# FT232.net
KiCad netlist of a schematic drawn in Altium Designer
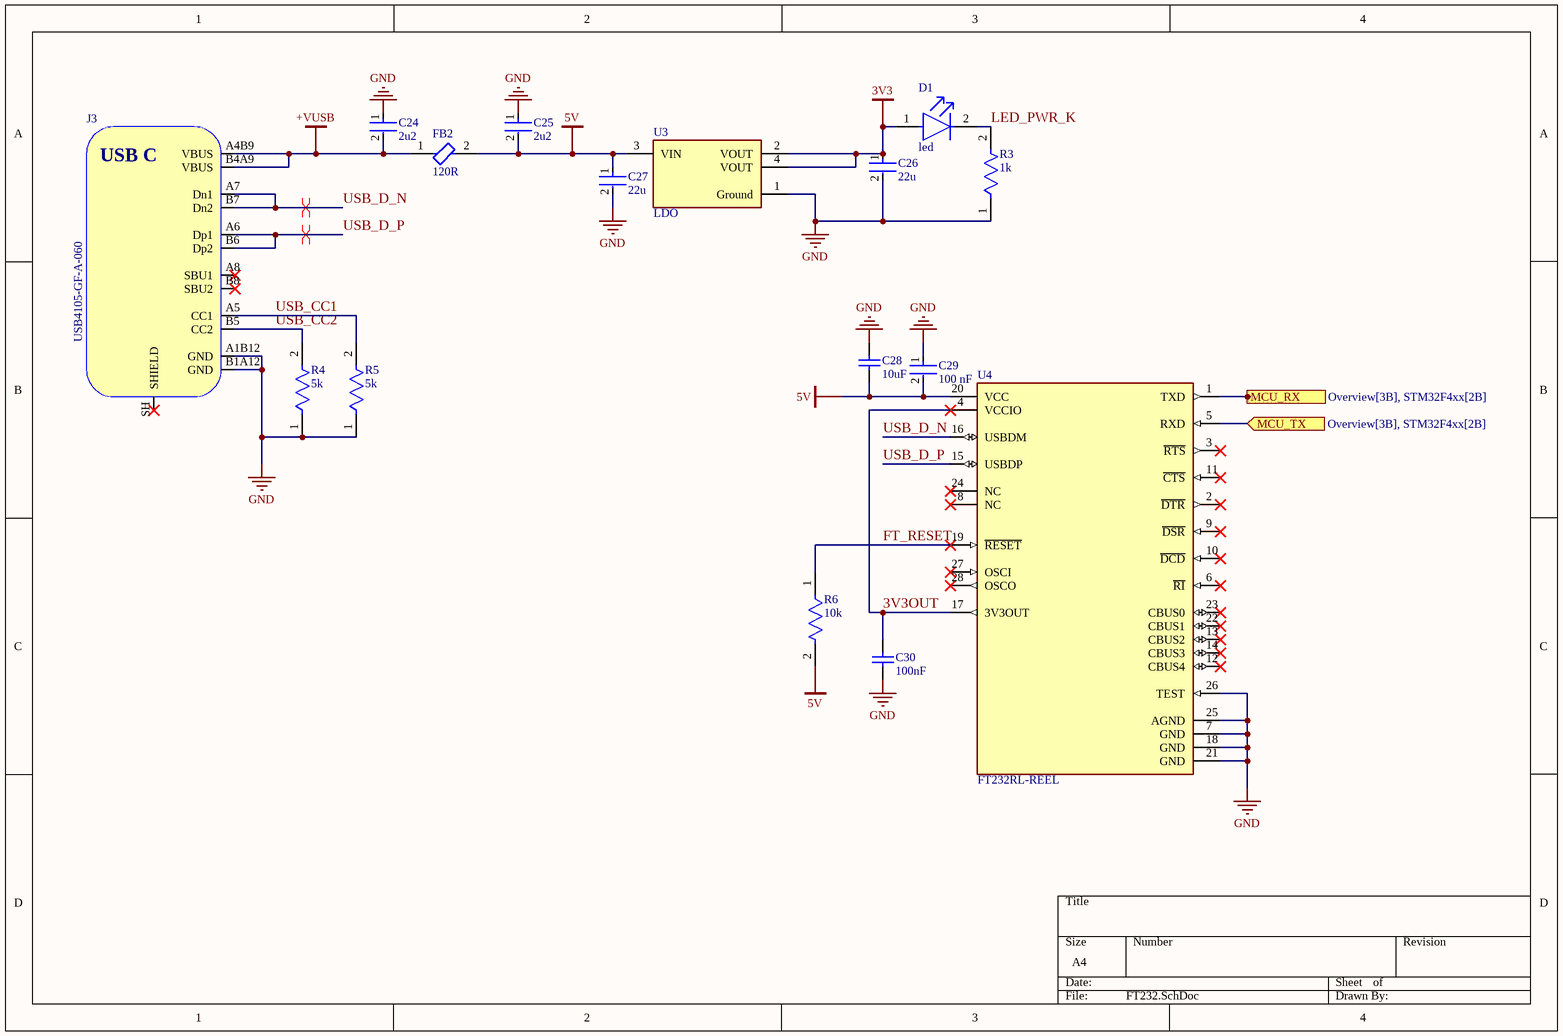
[diagram p0: FT232.SchDoc]

(export (version "E")
  (design (tool "Eeschema 10.0.6"))
  (components
    (comp (ref "C24")
      (value "2u2")
      (footprint "FP-CC0603-DA-MFG")
      (description "CAP CER 2.2UF 16V X5R 0603")
      (fields (field (name "TOLERANCE") "0.2") (field (name "MANUFACTURER PART NUMBER") "CC0603MRX5R7BB225"))
      (libsource (lib "Altium Content Vault") (part "11868f565c42a9108669ba33697ecf6"))
    )
    (comp (ref "C25")
      (value "2u2")
      (footprint "FP-CC0603-DA-MFG")
      (description "CAP CER 2.2UF 16V X5R 0603")
      (fields (field (name "TOLERANCE") "0.2") (field (name "MANUFACTURER PART NUMBER") "CC0603MRX5R7BB225"))
      (libsource (lib "Altium Content Vault") (part "11868f565c42a9108669ba33697ecf6"))
    )
    (comp (ref "C26")
      (value "22u")
      (footprint "FP-GRM21B-0_2-e0_2_0_7-IPC_C")
      (description "Chip Multilayer Ceramic Capacitors for General Purpose, 0805, 22uF, X5R, 15%, 20%, 16V")
      (fields (field (name "TOLERANCE") "20%"))
      (libsource (lib "Altium Content Vault") (part "b4654b650e69147ec39a6b967a45e02"))
    )
    (comp (ref "C27")
      (value "22u")
      (footprint "FP-GRM21B-0_2-e0_2_0_7-IPC_C")
      (description "Chip Multilayer Ceramic Capacitors for General Purpose, 0805, 22uF, X5R, 15%, 20%, 16V")
      (fields (field (name "TOLERANCE") "20%"))
      (libsource (lib "Altium Content Vault") (part "b4654b650e69147ec39a6b967a45e02"))
    )
    (comp (ref "C28")
      (value "10uF")
      (footprint "CAPC0603(1608)100_M")
      (description "CAP 10uF 6.3V ±10% 0603 (1608 Metric) Thickness 1mm SMD")
      (fields (field (name "TOLERANCE") "Â±10%"))
      (libsource (lib "Altium Content Vault") (part "CAP"))
    )
    (comp (ref "C29")
      (value "100 nF")
      (footprint "FP-C0402-BB-MFG")
      (description "CAP CER 0.1UF 25V X5R 0402")
      (fields
        (field (name "TOLERANCE") "0.2")
        (field (name "OCTOPART") "https://octopart.com/c0402c104m3pac7867-kemet-84304880")
      )
      (libsource (lib "Altium Content Vault") (part "b4654b650e69147ec39a6b967a45e02"))
    )
    (comp (ref "C30")
      (value "100nF")
      (footprint "CAPC2013X145X50ML20T25")
      (fields (field (name "MANUFACTURER") "Kemet") (field (name "PART NUMBER") "C0805C104K5RACTM"))
      (libsource (lib "Altium Content Vault") (part "CAP"))
    )
    (comp (ref "D1")
      (value "led")
      (footprint "FP-SM0402GC-MFG")
      (description "LED GREEN CLEAR 0402 SMD")
      (libsource (lib "Altium Content Vault") (part "ab1c01a81903e929fc6c44469aada92"))
    )
    (comp (ref "FB2")
      (value "120R")
      (footprint "FP-BLM21-0_2-t0_85-e0_5-IPC_C")
      (description "Chip Ferrite Bead, 0805, 60Ω @ 100MHz, 0.02Ω, 25%, 1.9A")
      (libsource (lib "Altium Content Vault") (part "5f30dd21d616792df468990f7003faa"))
    )
    (comp (ref "J3")
      (value "USB4105-GF-A-060")
      (footprint "USB4105-GF-A-060")
      (description "USB Connector Type C SMT 12 Pin")
      (fields (field (name "MANUFACTURER") "GCT"))
      (libsource (lib "Schematic-Lib-PhilsLab") (part "USB4105-GF-A-060"))
    )
    (comp (ref "R3")
      (value "1k")
      (footprint "FP-MCS0402-IPC_C")
      (description "RES SMD 1.2K OHM 1% 1/10W 0402")
      (fields (field (name "TOLERANCE") "0.1%"))
      (libsource (lib "Altium Content Vault") (part "1029c3af85768c4190bb7ad29bc67b5"))
    )
    (comp (ref "R4")
      (value "5k")
      (footprint "FP-TFCR0603-IPC_A")
      (description "RES Thin Film,  4kΩ, 0.1%, 0.1W, 25ppm/°C, 0603")
      (libsource (lib "Altium Content Vault") (part "1029c3af85768c4190bb7ad29bc67b5"))
    )
    (comp (ref "R5")
      (value "5k")
      (footprint "FP-TFCR0603-IPC_A")
      (description "RES Thin Film,  4kΩ, 0.1%, 0.1W, 25ppm/°C, 0603")
      (libsource (lib "Altium Content Vault") (part "1029c3af85768c4190bb7ad29bc67b5"))
    )
    (comp (ref "R6")
      (value "10k")
      (footprint "FP-AC0603-IPC_A")
      (description "RES 10kΩ 5.00% 0.2W 0603")
      (libsource (lib "Altium Content Vault") (part "1029c3af85768c4190bb7ad29bc67b5"))
    )
    (comp (ref "U3")
      (value "LDO")
      (footprint "FP-AMS1117-IPC_C")
      (description "LDO Voltage Regulators 1A, 3.3V")
      (fields
        (field (name "MANUFACTURER PART NUMBER") "AMS1117-3.3")
        (field (name "OCTOPART") "https://octopart.com/ams1117-3.3-advanced+monolithic+systems-25899300")
      )
      (libsource (lib "Altium Content Vault") (part "8bdbb5f8e77002000e30dd2845d0354"))
    )
    (comp (ref "U4")
      (value "FT232RL-REEL")
      (footprint "FP-SSOP-28-MFG")
      (description "IC USB FS SERIAL UART 28-SSOP")
      (fields (field (name "VOLTAGE") "5V"))
      (libsource (lib "Altium Content Vault") (part "fa727c664f4d88ca0f1b580aa0dd901"))
    )
  )
  (nets
    (net (code "1") (name "+VUSB") (class "Default")
      (node (ref "C24") (pin "2") (pinfunction "2_2") (pintype "passive"))
      (node (ref "FB2") (pin "1") (pinfunction "1_1") (pintype "passive"))
      (node (ref "J3") (pin "A4B9") (pinfunction "VBUS_A4B9") (pintype "passive"))
      (node (ref "J3") (pin "B4A9") (pinfunction "VBUS_B4A9") (pintype "passive"))
    )
    (net (code "2") (name "/3V3OUT") (class "Default")
      (node (ref "C30") (pin "2") (pinfunction "2_2") (pintype "passive"))
      (node (ref "U4") (pin "17") (pinfunction "3V3OUT_17") (pintype "output"))
      (node (ref "U4") (pin "4") (pinfunction "VCCIO_4") (pintype "power_in"))
    )
    (net (code "3") (name "/FT_RESET") (class "Default")
      (node (ref "R6") (pin "1") (pinfunction "1_1") (pintype "passive"))
      (node (ref "U4") (pin "19") (pinfunction "~{RESET}_19") (pintype "input"))
    )
    (net (code "4") (name "/LED_PWR_K") (class "Default")
      (node (ref "D1") (pin "2") (pinfunction "C_2") (pintype "passive"))
      (node (ref "R3") (pin "2") (pinfunction "2_2") (pintype "passive"))
    )
    (net (code "5") (name "/MCU_RX") (class "Default")
      (node (ref "U4") (pin "1") (pinfunction "TXD_1") (pintype "output"))
    )
    (net (code "6") (name "/MCU_TX") (class "Default")
      (node (ref "U4") (pin "5") (pinfunction "RXD_5") (pintype "input"))
    )
    (net (code "7") (name "/USB_CC1") (class "Default")
      (node (ref "J3") (pin "A5") (pinfunction "CC1_A5") (pintype "passive"))
      (node (ref "R5") (pin "2") (pinfunction "2_2") (pintype "passive"))
    )
    (net (code "8") (name "/USB_CC2") (class "Default")
      (node (ref "J3") (pin "B5") (pinfunction "CC2_B5") (pintype "passive"))
      (node (ref "R4") (pin "2") (pinfunction "2_2") (pintype "passive"))
    )
    (net (code "9") (name "/USB_D_N") (class "Default")
      (node (ref "J3") (pin "A7") (pinfunction "Dn1_A7") (pintype "passive"))
      (node (ref "J3") (pin "B7") (pinfunction "Dn2_B7") (pintype "passive"))
      (node (ref "U4") (pin "16") (pinfunction "USBDM_16") (pintype "bidirectional"))
    )
    (net (code "10") (name "/USB_D_P") (class "Default")
      (node (ref "J3") (pin "A6") (pinfunction "Dp1_A6") (pintype "passive"))
      (node (ref "J3") (pin "B6") (pinfunction "Dp2_B6") (pintype "passive"))
      (node (ref "U4") (pin "15") (pinfunction "USBDP_15") (pintype "bidirectional"))
    )
    (net (code "11") (name "3V3") (class "Default")
      (node (ref "C26") (pin "1") (pinfunction "1_1") (pintype "passive"))
      (node (ref "D1") (pin "1") (pinfunction "A_1") (pintype "passive"))
      (node (ref "U3") (pin "2") (pinfunction "VOUT_2") (pintype "passive"))
      (node (ref "U3") (pin "4") (pinfunction "VOUT_4") (pintype "passive"))
    )
    (net (code "12") (name "5V") (class "Default")
      (node (ref "C25") (pin "2") (pinfunction "2_2") (pintype "passive"))
      (node (ref "C27") (pin "1") (pinfunction "1_1") (pintype "passive"))
      (node (ref "C28") (pin "1") (pinfunction "1_1") (pintype "passive"))
      (node (ref "C29") (pin "2") (pinfunction "2_2") (pintype "passive"))
      (node (ref "FB2") (pin "2") (pinfunction "2_2") (pintype "passive"))
      (node (ref "R6") (pin "2") (pinfunction "2_2") (pintype "passive"))
      (node (ref "U3") (pin "3") (pinfunction "VIN_3") (pintype "power_in"))
      (node (ref "U4") (pin "20") (pinfunction "VCC_20") (pintype "power_in"))
    )
    (net (code "13") (name "GND") (class "Default")
      (node (ref "C24") (pin "1") (pinfunction "1_1") (pintype "passive"))
      (node (ref "C25") (pin "1") (pinfunction "1_1") (pintype "passive"))
      (node (ref "C26") (pin "2") (pinfunction "2_2") (pintype "passive"))
      (node (ref "C27") (pin "2") (pinfunction "2_2") (pintype "passive"))
      (node (ref "C28") (pin "2") (pinfunction "2_2") (pintype "passive"))
      (node (ref "C29") (pin "1") (pinfunction "1_1") (pintype "passive"))
      (node (ref "C30") (pin "1") (pinfunction "1_1") (pintype "passive"))
      (node (ref "J3") (pin "A1B12") (pinfunction "GND_A1B12") (pintype "passive"))
      (node (ref "J3") (pin "B1A12") (pinfunction "GND_B1A12") (pintype "passive"))
      (node (ref "R3") (pin "1") (pinfunction "1_1") (pintype "passive"))
      (node (ref "R4") (pin "1") (pinfunction "1_1") (pintype "passive"))
      (node (ref "R5") (pin "1") (pinfunction "1_1") (pintype "passive"))
      (node (ref "U3") (pin "1") (pinfunction "Ground_1") (pintype "power_in"))
      (node (ref "U4") (pin "18") (pinfunction "GND_18") (pintype "power_in"))
      (node (ref "U4") (pin "21") (pinfunction "GND_21") (pintype "power_in"))
      (node (ref "U4") (pin "25") (pinfunction "AGND_25") (pintype "power_in"))
      (node (ref "U4") (pin "26") (pinfunction "TEST_26") (pintype "input"))
      (node (ref "U4") (pin "7") (pinfunction "GND_7") (pintype "power_in"))
    )
    (net (code "14") (name "unconnected-(J3-SBU1-PadA8)") (class "Default")
      (node (ref "J3") (pin "A8") (pinfunction "SBU1_A8") (pintype "passive+no_connect"))
    )
    (net (code "15") (name "unconnected-(J3-SBU2-PadB8)") (class "Default")
      (node (ref "J3") (pin "B8") (pinfunction "SBU2_B8") (pintype "passive+no_connect"))
    )
    (net (code "16") (name "unconnected-(J3-SHIELD-PadSH)") (class "Default")
      (node (ref "J3") (pin "SH") (pinfunction "SHIELD_SH") (pintype "passive+no_connect"))
    )
    (net (code "17") (name "unconnected-(U4-CBUS0-Pad23)") (class "Default")
      (node (ref "U4") (pin "23") (pinfunction "CBUS0_23") (pintype "bidirectional+no_connect"))
    )
    (net (code "18") (name "unconnected-(U4-CBUS1-Pad22)") (class "Default")
      (node (ref "U4") (pin "22") (pinfunction "CBUS1_22") (pintype "bidirectional+no_connect"))
    )
    (net (code "19") (name "unconnected-(U4-CBUS2-Pad13)") (class "Default")
      (node (ref "U4") (pin "13") (pinfunction "CBUS2_13") (pintype "bidirectional+no_connect"))
    )
    (net (code "20") (name "unconnected-(U4-CBUS3-Pad14)") (class "Default")
      (node (ref "U4") (pin "14") (pinfunction "CBUS3_14") (pintype "bidirectional+no_connect"))
    )
    (net (code "21") (name "unconnected-(U4-CBUS4-Pad12)") (class "Default")
      (node (ref "U4") (pin "12") (pinfunction "CBUS4_12") (pintype "bidirectional+no_connect"))
    )
    (net (code "22") (name "unconnected-(U4-NC-Pad8)") (class "Default")
      (node (ref "U4") (pin "8") (pinfunction "NC_8") (pintype "passive+no_connect"))
    )
    (net (code "23") (name "unconnected-(U4-NC-Pad24)") (class "Default")
      (node (ref "U4") (pin "24") (pinfunction "NC_24") (pintype "passive+no_connect"))
    )
    (net (code "24") (name "unconnected-(U4-OSCI-Pad27)") (class "Default")
      (node (ref "U4") (pin "27") (pinfunction "OSCI_27") (pintype "input+no_connect"))
    )
    (net (code "25") (name "unconnected-(U4-OSCO-Pad28)") (class "Default")
      (node (ref "U4") (pin "28") (pinfunction "OSCO_28") (pintype "output+no_connect"))
    )
    (net (code "26") (name "unconnected-(U4-~{CTS}-Pad11)") (class "Default")
      (node (ref "U4") (pin "11") (pinfunction "~{CTS}_11") (pintype "input+no_connect"))
    )
    (net (code "27") (name "unconnected-(U4-~{DCD}-Pad10)") (class "Default")
      (node (ref "U4") (pin "10") (pinfunction "~{DCD}_10") (pintype "input+no_connect"))
    )
    (net (code "28") (name "unconnected-(U4-~{DSR}-Pad9)") (class "Default")
      (node (ref "U4") (pin "9") (pinfunction "~{DSR}_9") (pintype "input+no_connect"))
    )
    (net (code "29") (name "unconnected-(U4-~{DTR}-Pad2)") (class "Default")
      (node (ref "U4") (pin "2") (pinfunction "~{DTR}_2") (pintype "output+no_connect"))
    )
    (net (code "30") (name "unconnected-(U4-~{RI}-Pad6)") (class "Default")
      (node (ref "U4") (pin "6") (pinfunction "~{RI}_6") (pintype "input+no_connect"))
    )
    (net (code "31") (name "unconnected-(U4-~{RTS}-Pad3)") (class "Default")
      (node (ref "U4") (pin "3") (pinfunction "~{RTS}_3") (pintype "output+no_connect"))
    )
  )
)
